# Instrumentation_amplifier_CC3220SF.net
KiCad netlist of a schematic drawn in EAGLE
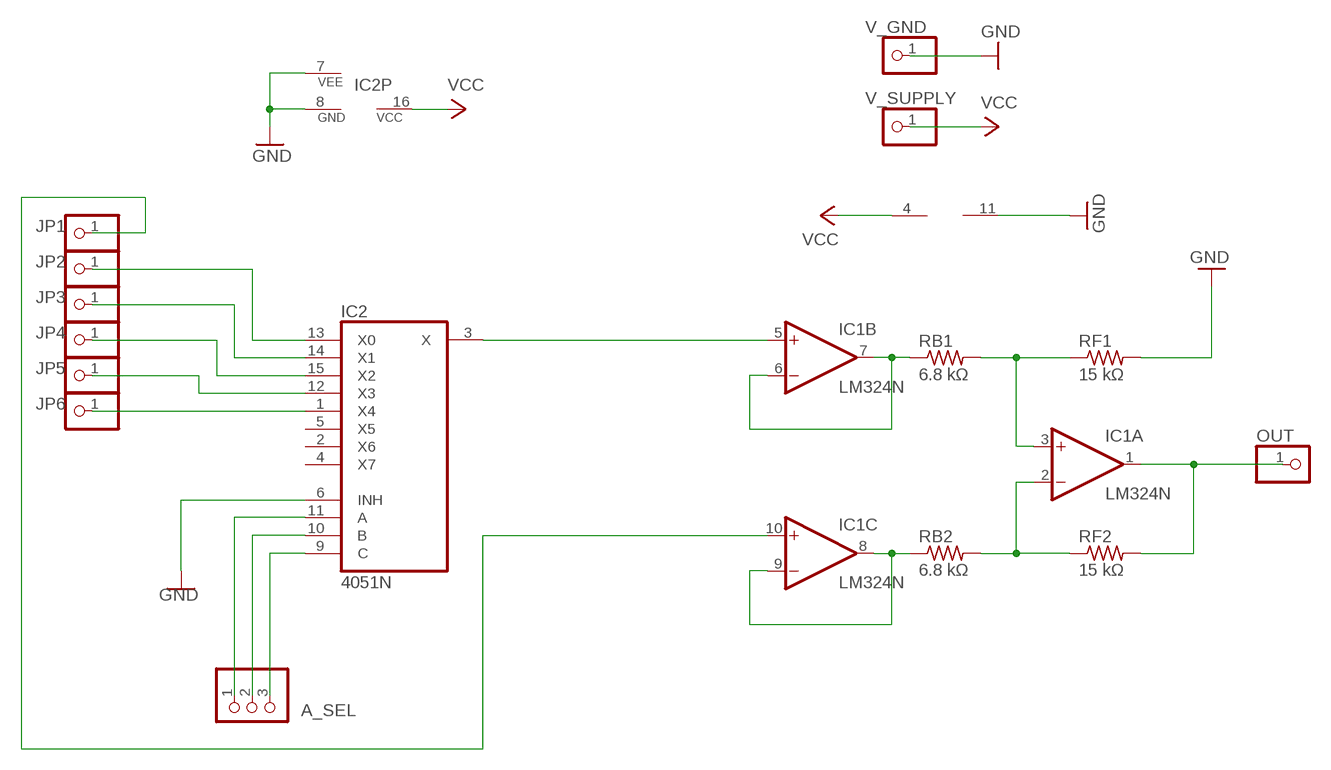
[diagram p0: schematic, sheet 1]

(export (version "E")
  (design (tool "Eeschema 10.0.6"))
  (components
    (comp (ref "A_SEL")
      (value "PINHD-1X3")
      (footprint "eagle-import:1X03")
      (libsource (lib "eagle-import") (part "PINHD-1X3"))
    )
    (comp (ref "IC1")
      (value "LM324N")
      (footprint "eagle-import:DIL14")
      (libsource (lib "eagle-import") (part "LM324N"))
    )
    (comp (ref "IC2")
      (value "4051N")
      (footprint "eagle-import:DIL16")
      (libsource (lib "eagle-import") (part "4051N"))
    )
    (comp (ref "JP1")
      (value "PINHD-1X1")
      (footprint "eagle-import:1X01")
      (libsource (lib "eagle-import") (part "PINHD-1X1"))
    )
    (comp (ref "JP2")
      (value "PINHD-1X1")
      (footprint "eagle-import:1X01")
      (libsource (lib "eagle-import") (part "PINHD-1X1"))
    )
    (comp (ref "JP3")
      (value "PINHD-1X1")
      (footprint "eagle-import:1X01")
      (libsource (lib "eagle-import") (part "PINHD-1X1"))
    )
    (comp (ref "JP4")
      (value "PINHD-1X1")
      (footprint "eagle-import:1X01")
      (libsource (lib "eagle-import") (part "PINHD-1X1"))
    )
    (comp (ref "JP5")
      (value "PINHD-1X1")
      (footprint "eagle-import:1X01")
      (libsource (lib "eagle-import") (part "PINHD-1X1"))
    )
    (comp (ref "JP6")
      (value "PINHD-1X1")
      (footprint "eagle-import:1X01")
      (libsource (lib "eagle-import") (part "PINHD-1X1"))
    )
    (comp (ref "OUT")
      (value "PINHD-1X1")
      (footprint "eagle-import:1X01")
      (libsource (lib "eagle-import") (part "PINHD-1X1"))
    )
    (comp (ref "RB1")
      (value "6.8 kΩ")
      (footprint "eagle-import:0204_7")
      (libsource (lib "eagle-import") (part "R-US_0204/7"))
    )
    (comp (ref "RB2")
      (value "6.8 kΩ")
      (footprint "eagle-import:0204_7")
      (libsource (lib "eagle-import") (part "R-US_0204/7"))
    )
    (comp (ref "RF1")
      (value "15 kΩ")
      (footprint "eagle-import:0204_7")
      (libsource (lib "eagle-import") (part "R-US_0204/7"))
    )
    (comp (ref "RF2")
      (value "15 kΩ")
      (footprint "eagle-import:0204_7")
      (libsource (lib "eagle-import") (part "R-US_0204/7"))
    )
    (comp (ref "V_GND")
      (value "PINHD-1X1")
      (footprint "eagle-import:1X01")
      (libsource (lib "eagle-import") (part "PINHD-1X1"))
    )
    (comp (ref "V_SUPPLY")
      (value "PINHD-1X1")
      (footprint "eagle-import:1X01")
      (libsource (lib "eagle-import") (part "PINHD-1X1"))
    )
  )
  (nets
    (net (code "1") (name "GND") (class "Default")
      (node (ref "IC1") (pin "11") (pinfunction "V-_11") (pintype "power_in"))
      (node (ref "IC2") (pin "6") (pinfunction "INH_6") (pintype "input"))
      (node (ref "IC2") (pin "7") (pinfunction "VEE_7") (pintype "power_in"))
      (node (ref "IC2") (pin "8") (pinfunction "GND_8") (pintype "power_in"))
      (node (ref "RF1") (pin "2") (pinfunction "2_2") (pintype "passive"))
      (node (ref "V_GND") (pin "1") (pinfunction "1_1") (pintype "passive"))
    )
    (net (code "2") (name "Net-(IC1A-+IN)") (class "Default")
      (node (ref "IC1") (pin "3") (pinfunction "+IN_3") (pintype "input"))
      (node (ref "RB1") (pin "2") (pinfunction "2_2") (pintype "passive"))
      (node (ref "RF1") (pin "1") (pinfunction "1_1") (pintype "passive"))
    )
    (net (code "3") (name "Net-(IC1A--IN)") (class "Default")
      (node (ref "IC1") (pin "2") (pinfunction "-IN_2") (pintype "input"))
      (node (ref "RB2") (pin "2") (pinfunction "2_2") (pintype "passive"))
      (node (ref "RF2") (pin "1") (pinfunction "1_1") (pintype "passive"))
    )
    (net (code "4") (name "Net-(IC1A-OUT)") (class "Default")
      (node (ref "IC1") (pin "1") (pinfunction "OUT_1") (pintype "output"))
      (node (ref "OUT") (pin "1") (pinfunction "1_1") (pintype "passive"))
      (node (ref "RF2") (pin "2") (pinfunction "2_2") (pintype "passive"))
    )
    (net (code "5") (name "Net-(IC1B-+IN)") (class "Default")
      (node (ref "IC1") (pin "5") (pinfunction "+IN_5") (pintype "input"))
      (node (ref "IC2") (pin "3") (pinfunction "X_3") (pintype "bidirectional"))
    )
    (net (code "6") (name "Net-(IC1B--IN)") (class "Default")
      (node (ref "IC1") (pin "6") (pinfunction "-IN_6") (pintype "input"))
      (node (ref "IC1") (pin "7") (pinfunction "OUT_7") (pintype "output"))
      (node (ref "RB1") (pin "1") (pinfunction "1_1") (pintype "passive"))
    )
    (net (code "7") (name "Net-(IC1C-+IN)") (class "Default")
      (node (ref "IC1") (pin "10") (pinfunction "+IN_10") (pintype "input"))
      (node (ref "JP1") (pin "1") (pinfunction "1_1") (pintype "passive"))
    )
    (net (code "8") (name "Net-(IC1C--IN)") (class "Default")
      (node (ref "IC1") (pin "8") (pinfunction "OUT_8") (pintype "output"))
      (node (ref "IC1") (pin "9") (pinfunction "-IN_9") (pintype "input"))
      (node (ref "RB2") (pin "1") (pinfunction "1_1") (pintype "passive"))
    )
    (net (code "9") (name "Net-(IC2A-A)") (class "Default")
      (node (ref "A_SEL") (pin "1") (pinfunction "1_1") (pintype "passive"))
      (node (ref "IC2") (pin "11") (pinfunction "A_11") (pintype "input"))
    )
    (net (code "10") (name "Net-(IC2A-B)") (class "Default")
      (node (ref "A_SEL") (pin "2") (pinfunction "2_2") (pintype "passive"))
      (node (ref "IC2") (pin "10") (pinfunction "B_10") (pintype "input"))
    )
    (net (code "11") (name "Net-(IC2A-C)") (class "Default")
      (node (ref "A_SEL") (pin "3") (pinfunction "3_3") (pintype "passive"))
      (node (ref "IC2") (pin "9") (pinfunction "C_9") (pintype "input"))
    )
    (net (code "12") (name "Net-(IC2A-X0)") (class "Default")
      (node (ref "IC2") (pin "13") (pinfunction "X0_13") (pintype "bidirectional"))
      (node (ref "JP2") (pin "1") (pinfunction "1_1") (pintype "passive"))
    )
    (net (code "13") (name "Net-(IC2A-X1)") (class "Default")
      (node (ref "IC2") (pin "14") (pinfunction "X1_14") (pintype "bidirectional"))
      (node (ref "JP3") (pin "1") (pinfunction "1_1") (pintype "passive"))
    )
    (net (code "14") (name "Net-(IC2A-X2)") (class "Default")
      (node (ref "IC2") (pin "15") (pinfunction "X2_15") (pintype "bidirectional"))
      (node (ref "JP4") (pin "1") (pinfunction "1_1") (pintype "passive"))
    )
    (net (code "15") (name "Net-(IC2A-X3)") (class "Default")
      (node (ref "IC2") (pin "12") (pinfunction "X3_12") (pintype "bidirectional"))
      (node (ref "JP5") (pin "1") (pinfunction "1_1") (pintype "passive"))
    )
    (net (code "16") (name "Net-(IC2A-X4)") (class "Default")
      (node (ref "IC2") (pin "1") (pinfunction "X4_1") (pintype "bidirectional"))
      (node (ref "JP6") (pin "1") (pinfunction "1_1") (pintype "passive"))
    )
    (net (code "17") (name "VCC") (class "Default")
      (node (ref "IC1") (pin "4") (pinfunction "V+_4") (pintype "power_in"))
      (node (ref "IC2") (pin "16") (pinfunction "VCC_16") (pintype "power_in"))
      (node (ref "V_SUPPLY") (pin "1") (pinfunction "1_1") (pintype "passive"))
    )
    (net (code "18") (name "unconnected-(IC2A-X5-Pad5)") (class "Default")
      (node (ref "IC2") (pin "5") (pinfunction "X5_5") (pintype "bidirectional"))
    )
    (net (code "19") (name "unconnected-(IC2A-X6-Pad2)") (class "Default")
      (node (ref "IC2") (pin "2") (pinfunction "X6_2") (pintype "bidirectional"))
    )
    (net (code "20") (name "unconnected-(IC2A-X7-Pad4)") (class "Default")
      (node (ref "IC2") (pin "4") (pinfunction "X7_4") (pintype "bidirectional"))
    )
  )
)
